# BW1098OAK_USB.net
KiCad netlist of a schematic drawn in Altium Designer
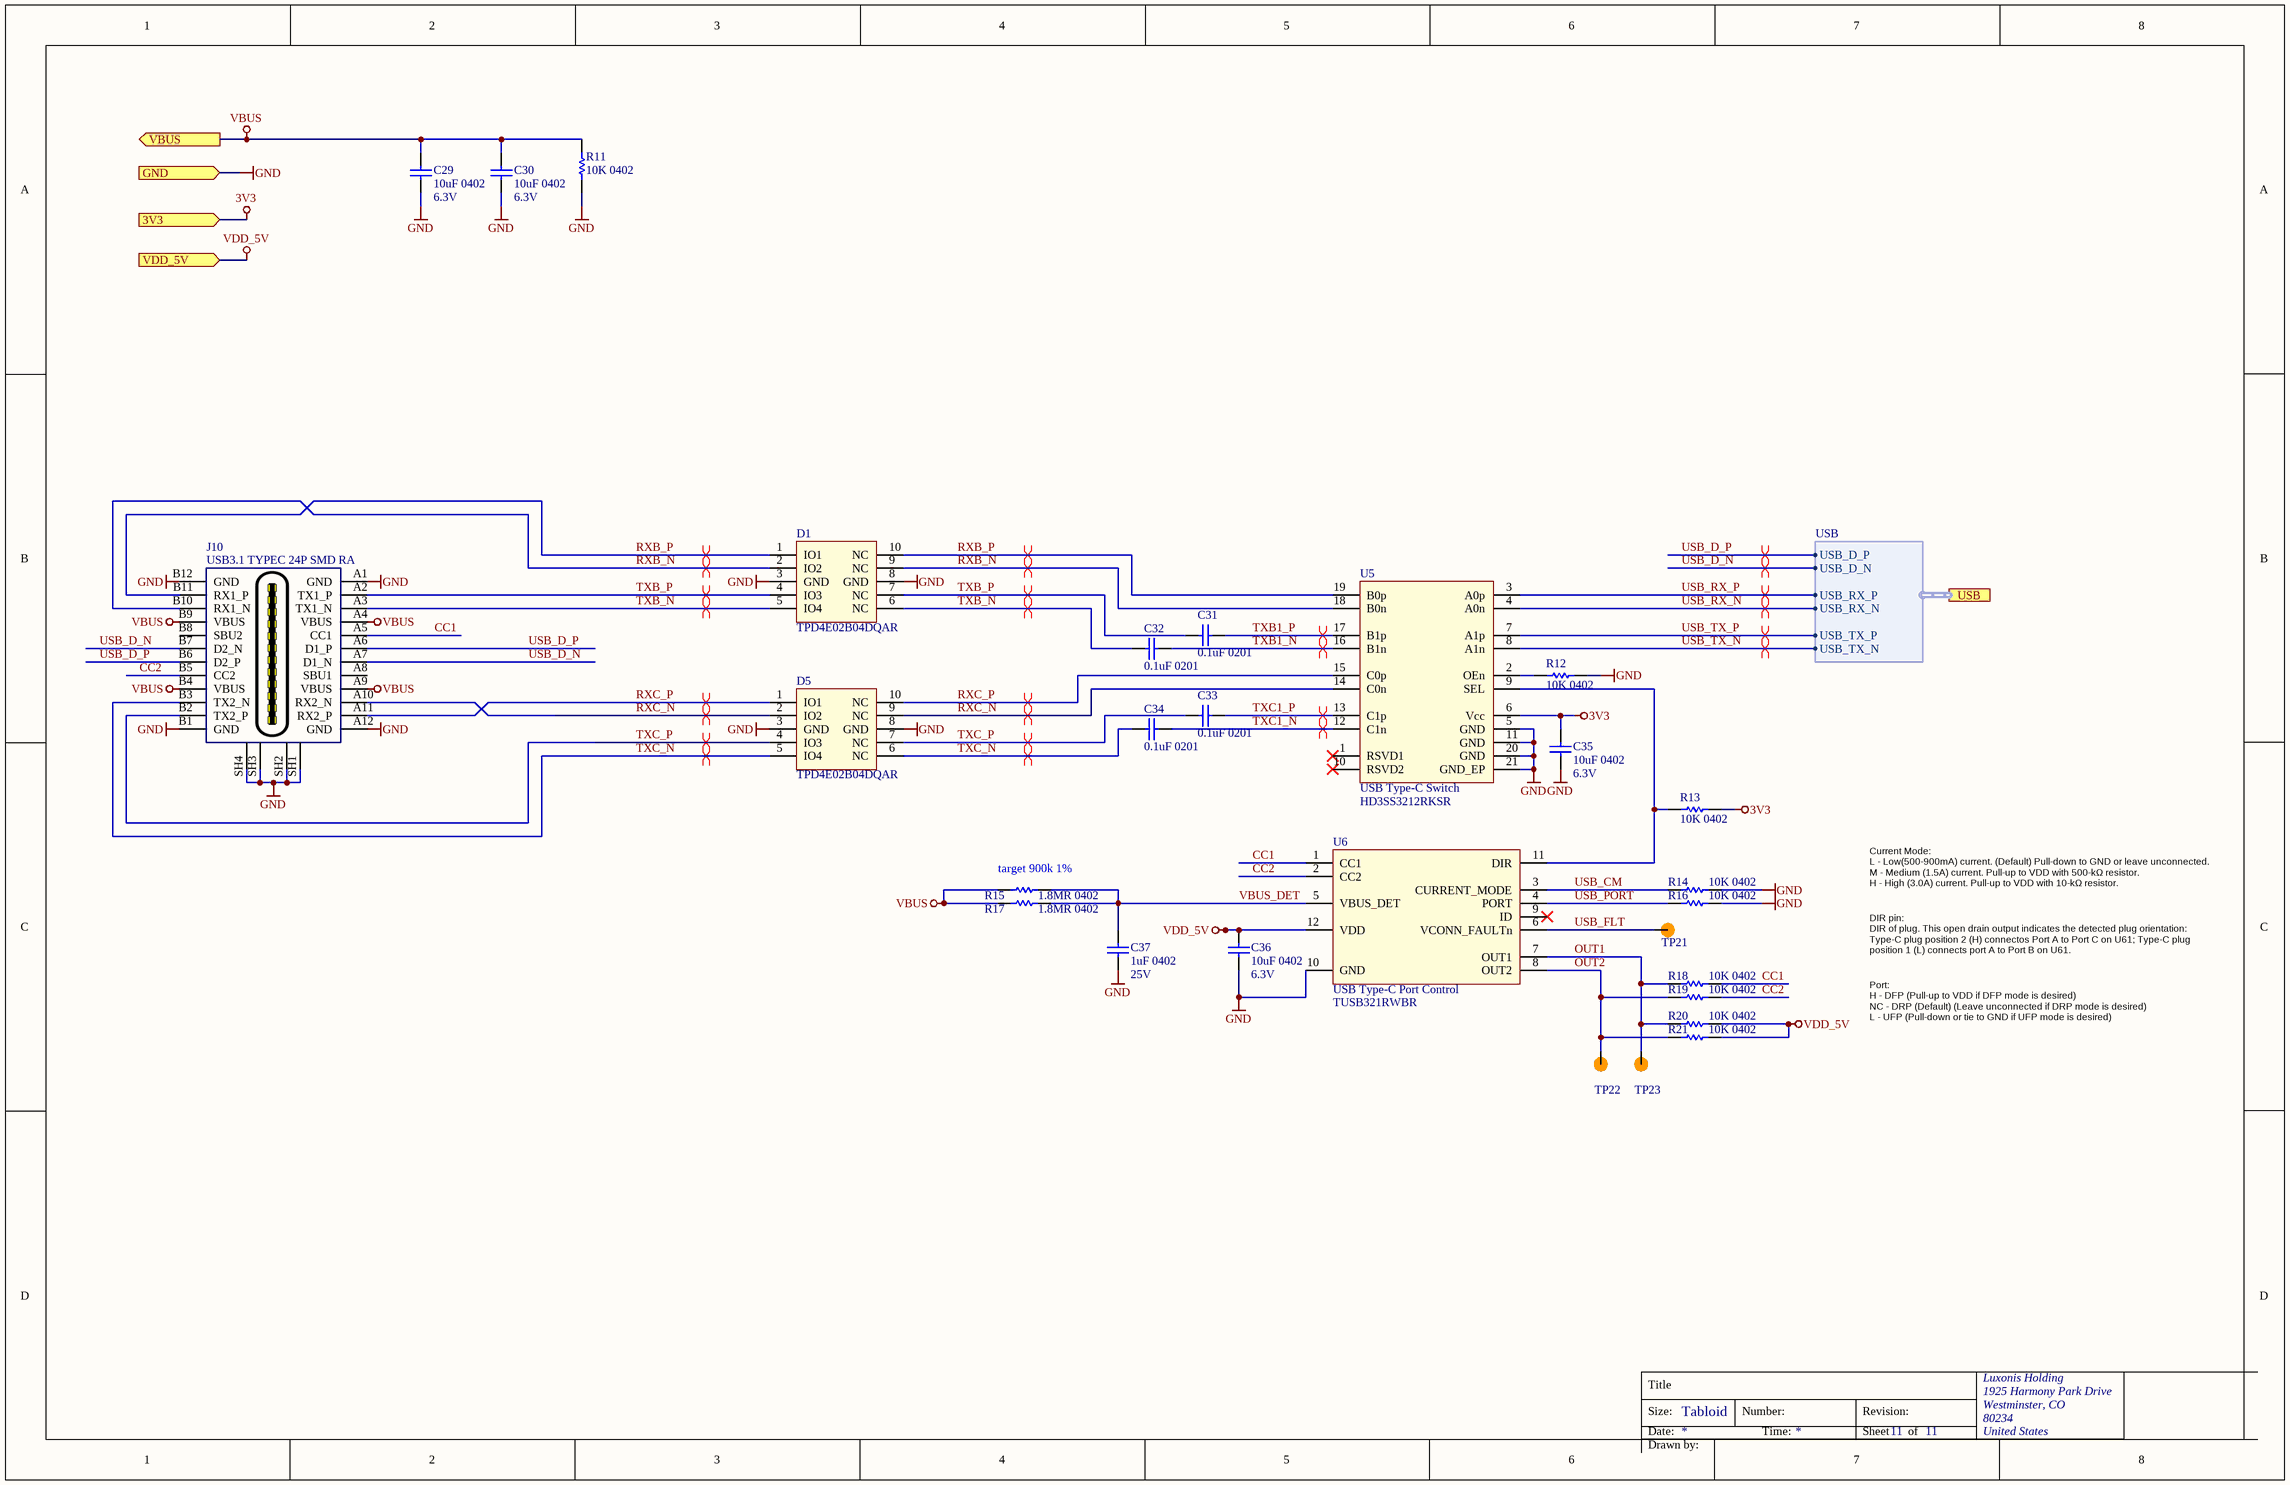
[diagram p0: BW1098OAK_USB.SchDoc]

(export (version "E")
  (design (tool "Eeschema 10.0.6"))
  (components
    (comp (ref "C29")
      (value "10uF 0402")
      (footprint "CAP_Altium_Vault_Generic:CAPC0402(1005)70_L")
      (description "CAP CER 10UF 6.3V X5R 0402 20%")
      (fields (field (name "TOLERANCE") "20%") (field (name "VOLTAGE RATING") "6.3V"))
      (libsource (lib "LuxonisMaster") (part "GRM155R60J106ME15D"))
    )
    (comp (ref "C30")
      (value "10uF 0402")
      (footprint "CAP_Altium_Vault_Generic:CAPC0402(1005)70_L")
      (description "CAP CER 10UF 6.3V X5R 0402 20%")
      (fields (field (name "TOLERANCE") "20%") (field (name "VOLTAGE RATING") "6.3V"))
      (libsource (lib "LuxonisMaster") (part "GRM155R60J106ME15D"))
    )
    (comp (ref "C31")
      (value "0.1uF 0201")
      (footprint "CAP_Altium_Vault_Generic:CAPC0201(0603)33_L")
      (description "CAP CER 0.1UF 10V X5R 0201")
      (fields (field (name "TOLERANCE") "10%") (field (name "VOLTAGE") "10V"))
      (libsource (lib "LuxonisMaster") (part "GRM033R61A104KE15D"))
    )
    (comp (ref "C32")
      (value "0.1uF 0201")
      (footprint "CAP_Altium_Vault_Generic:CAPC0201(0603)33_L")
      (description "CAP CER 0.1UF 10V X5R 0201")
      (fields (field (name "TOLERANCE") "10%") (field (name "VOLTAGE") "10V"))
      (libsource (lib "LuxonisMaster") (part "GRM033R61A104KE15D"))
    )
    (comp (ref "C33")
      (value "0.1uF 0201")
      (footprint "CAP_Altium_Vault_Generic:CAPC0201(0603)33_L")
      (description "CAP CER 0.1UF 10V X5R 0201")
      (fields (field (name "TOLERANCE") "10%") (field (name "VOLTAGE") "10V"))
      (libsource (lib "LuxonisMaster") (part "GRM033R61A104KE15D"))
    )
    (comp (ref "C34")
      (value "0.1uF 0201")
      (footprint "CAP_Altium_Vault_Generic:CAPC0201(0603)33_L")
      (description "CAP CER 0.1UF 10V X5R 0201")
      (fields (field (name "TOLERANCE") "10%") (field (name "VOLTAGE") "10V"))
      (libsource (lib "LuxonisMaster") (part "GRM033R61A104KE15D"))
    )
    (comp (ref "C35")
      (value "10uF 0402")
      (footprint "CAP_Altium_Vault_Generic:CAPC0402(1005)70_L")
      (description "CAP CER 10UF 6.3V X5R 0402 20%")
      (fields (field (name "TOLERANCE") "20%") (field (name "VOLTAGE RATING") "6.3V"))
      (libsource (lib "LuxonisMaster") (part "GRM155R60J106ME15D"))
    )
    (comp (ref "C36")
      (value "10uF 0402")
      (footprint "CAP_Altium_Vault_Generic:CAPC0402(1005)70_L")
      (description "CAP CER 10UF 6.3V X5R 0402 20%")
      (fields (field (name "TOLERANCE") "20%") (field (name "VOLTAGE RATING") "6.3V"))
      (libsource (lib "LuxonisMaster") (part "GRM155R60J106ME15D"))
    )
    (comp (ref "C37")
      (value "1uF 0402")
      (footprint "CAP_Altium_Vault_Generic:CAPC0402(1005)70_N")
      (description "CAP CER 1UF 25V X5R 0402 10%")
      (fields
        (field (name "TOLERANCE") "10%")
        (field (name "VOLTAGE") "25V")
        (field (name "VOLTAGE RATING") "25V")
      )
      (libsource (lib "LuxonisMaster") (part "GRM155R61E105KA12D"))
    )
    (comp (ref "D1")
      (value "TPD4E02B04DQAR")
      (footprint "LuxonisMaster:TPD4E02B04DQAR")
      (libsource (lib "LuxonisMaster") (part "TPD4E02B04DQAR"))
    )
    (comp (ref "D5")
      (value "TPD4E02B04DQAR")
      (footprint "LuxonisMaster:TPD4E02B04DQAR")
      (libsource (lib "LuxonisMaster") (part "TPD4E02B04DQAR"))
    )
    (comp (ref "J10")
      (value "USB3.1 TYPEC 24P SMD RA")
      (footprint "LuxonisMaster:105450-0101")
      (description "CONN RCP USB3.1 TYPEC 24P SMD RA")
      (libsource (lib "LuxonisMaster") (part "105450-0101"))
    )
    (comp (ref "R11")
      (value "10K 0402")
      (footprint "RES_Altium_Vault_Generic:RESC0402(1005)_L")
      (fields (field (name "TOLERANCE") "1%"))
      (libsource (lib "LuxonisMaster") (part "RC0402FR-1310KL"))
    )
    (comp (ref "R12")
      (value "10K 0402")
      (footprint "RES_Altium_Vault_Generic:RESC0402(1005)_L")
      (fields (field (name "TOLERANCE") "1%"))
      (libsource (lib "LuxonisMaster") (part "RC0402FR-1310KL"))
    )
    (comp (ref "R13")
      (value "10K 0402")
      (footprint "RES_Altium_Vault_Generic:RESC0402(1005)_L")
      (fields (field (name "TOLERANCE") "1%"))
      (libsource (lib "LuxonisMaster") (part "RC0402FR-1310KL"))
    )
    (comp (ref "R14")
      (value "10K 0402")
      (footprint "RES_Altium_Vault_Generic:RESC0402(1005)_L")
      (fields (field (name "TOLERANCE") "1%"))
      (libsource (lib "LuxonisMaster") (part "RC0402FR-1310KL"))
    )
    (comp (ref "R15")
      (value "1.8MR 0402")
      (footprint "RES_Altium_Vault_Generic:RESC0402(1005)_L")
      (description "RES SMD 1.8M OHM 1% 1/16W 0402")
      (fields (field (name "TOLERANCE") "1%"))
      (libsource (lib "LuxonisMaster") (part "CRCW04021M80FKED"))
    )
    (comp (ref "R16")
      (value "10K 0402")
      (footprint "RES_Altium_Vault_Generic:RESC0402(1005)_L")
      (fields (field (name "TOLERANCE") "1%"))
      (libsource (lib "LuxonisMaster") (part "RC0402FR-1310KL"))
    )
    (comp (ref "R17")
      (value "1.8MR 0402")
      (footprint "RES_Altium_Vault_Generic:RESC0402(1005)_L")
      (description "RES SMD 1.8M OHM 1% 1/16W 0402")
      (fields (field (name "TOLERANCE") "1%"))
      (libsource (lib "LuxonisMaster") (part "CRCW04021M80FKED"))
    )
    (comp (ref "R18")
      (value "10K 0402")
      (footprint "RES_Altium_Vault_Generic:RESC0402(1005)_L")
      (fields (field (name "TOLERANCE") "1%"))
      (libsource (lib "LuxonisMaster") (part "RC0402FR-1310KL"))
    )
    (comp (ref "R19")
      (value "10K 0402")
      (footprint "RES_Altium_Vault_Generic:RESC0402(1005)_L")
      (fields (field (name "TOLERANCE") "1%"))
      (libsource (lib "LuxonisMaster") (part "RC0402FR-1310KL"))
    )
    (comp (ref "R20")
      (value "10K 0402")
      (footprint "RES_Altium_Vault_Generic:RESC0402(1005)_L")
      (fields (field (name "TOLERANCE") "1%"))
      (libsource (lib "LuxonisMaster") (part "RC0402FR-1310KL"))
    )
    (comp (ref "R21")
      (value "10K 0402")
      (footprint "RES_Altium_Vault_Generic:RESC0402(1005)_L")
      (fields (field (name "TOLERANCE") "1%"))
      (libsource (lib "LuxonisMaster") (part "RC0402FR-1310KL"))
    )
    (comp (ref "TP21")
      (value "TP100_200_NS")
      (footprint "LuxonisMaster:TP100_200_NS")
      (libsource (lib "LuxonisMaster") (part "TEST_POINT"))
    )
    (comp (ref "TP22")
      (value "TP100_200_NS")
      (footprint "LuxonisMaster:TP100_200_NS")
      (libsource (lib "LuxonisMaster") (part "TEST_POINT"))
    )
    (comp (ref "TP23")
      (value "TP100_200_NS")
      (footprint "LuxonisMaster:TP100_200_NS")
      (libsource (lib "LuxonisMaster") (part "TEST_POINT"))
    )
    (comp (ref "U5")
      (value "USB Type-C Switch")
      (footprint "LuxonisMaster:HD3SS3212RKSR")
      (description "IC MUX 2:1 8 OHM 20VQFN")
      (fields (field (name "MANUFACTURER PART NUMBER 1") "HD3SS3212RKSR"))
      (libsource (lib "LuxonisMaster") (part "HD3SS3212RKSR"))
    )
    (comp (ref "U6")
      (value "USB Type-C Port Control")
      (footprint "LuxonisMaster:TUSB321RWBR")
      (description "IC USB PORT CONTROL TYPE-C 12X2Q")
      (fields (field (name "MANUFACTURER PART NUMBER 1") "TUSB321RWBR"))
      (libsource (lib "LuxonisMaster") (part "TUSB321RWBR"))
    )
  )
  (nets
    (net (code "2") (name "/CC1") (class "Default")
      (node (ref "J10") (pin "A5") (pinfunction "CC1_A5") (pintype "passive"))
      (node (ref "R18") (pin "2") (pinfunction "2_2") (pintype "passive"))
      (node (ref "U6") (pin "1") (pinfunction "CC1_1") (pintype "passive"))
    )
    (net (code "3") (name "/CC2") (class "Default")
      (node (ref "J10") (pin "B5") (pinfunction "CC2_B5") (pintype "passive"))
      (node (ref "R19") (pin "2") (pinfunction "2_2") (pintype "passive"))
      (node (ref "U6") (pin "2") (pinfunction "CC2_2") (pintype "passive"))
    )
    (net (code "4") (name "/OUT1") (class "Default")
      (node (ref "R18") (pin "1") (pinfunction "1_1") (pintype "passive"))
      (node (ref "R20") (pin "1") (pinfunction "1_1") (pintype "passive"))
      (node (ref "TP23") (pin "1") (pintype "passive"))
      (node (ref "U6") (pin "7") (pinfunction "OUT1_7") (pintype "passive"))
    )
    (net (code "5") (name "/OUT2") (class "Default")
      (node (ref "R19") (pin "1") (pinfunction "1_1") (pintype "passive"))
      (node (ref "R21") (pin "1") (pinfunction "1_1") (pintype "passive"))
      (node (ref "TP22") (pin "1") (pintype "passive"))
      (node (ref "U6") (pin "8") (pinfunction "OUT2_8") (pintype "passive"))
    )
    (net (code "6") (name "/RXB_N") (class "Default")
      (node (ref "D1") (pin "2") (pinfunction "IO2_2") (pintype "passive"))
      (node (ref "D1") (pin "9") (pinfunction "NC_9") (pintype "passive"))
      (node (ref "J10") (pin "B10") (pinfunction "RX1_N_B10") (pintype "passive"))
      (node (ref "U5") (pin "18") (pinfunction "B0n_18") (pintype "passive"))
    )
    (net (code "7") (name "/RXB_P") (class "Default")
      (node (ref "D1") (pin "1") (pinfunction "IO1_1") (pintype "passive"))
      (node (ref "D1") (pin "10") (pinfunction "NC_10") (pintype "passive"))
      (node (ref "J10") (pin "B11") (pinfunction "RX1_P_B11") (pintype "passive"))
      (node (ref "U5") (pin "19") (pinfunction "B0p_19") (pintype "passive"))
    )
    (net (code "8") (name "/RXC_N") (class "Default")
      (node (ref "D5") (pin "2") (pinfunction "IO2_2") (pintype "passive"))
      (node (ref "D5") (pin "9") (pinfunction "NC_9") (pintype "passive"))
      (node (ref "J10") (pin "A10") (pinfunction "RX2_N_A10") (pintype "passive"))
      (node (ref "U5") (pin "14") (pinfunction "C0n_14") (pintype "passive"))
    )
    (net (code "9") (name "/RXC_P") (class "Default")
      (node (ref "D5") (pin "1") (pinfunction "IO1_1") (pintype "passive"))
      (node (ref "D5") (pin "10") (pinfunction "NC_10") (pintype "passive"))
      (node (ref "J10") (pin "A11") (pinfunction "RX2_P_A11") (pintype "passive"))
      (node (ref "U5") (pin "15") (pinfunction "C0p_15") (pintype "passive"))
    )
    (net (code "10") (name "/TXB1_N") (class "Default")
      (node (ref "C32") (pin "2") (pinfunction "2_2") (pintype "passive"))
      (node (ref "U5") (pin "16") (pinfunction "B1n_16") (pintype "passive"))
    )
    (net (code "11") (name "/TXB1_P") (class "Default")
      (node (ref "C31") (pin "2") (pinfunction "2_2") (pintype "passive"))
      (node (ref "U5") (pin "17") (pinfunction "B1p_17") (pintype "passive"))
    )
    (net (code "12") (name "/TXB_N") (class "Default")
      (node (ref "C32") (pin "1") (pinfunction "1_1") (pintype "passive"))
      (node (ref "D1") (pin "5") (pinfunction "IO4_5") (pintype "passive"))
      (node (ref "D1") (pin "6") (pinfunction "NC_6") (pintype "passive"))
      (node (ref "J10") (pin "A3") (pinfunction "TX1_N_A3") (pintype "passive"))
    )
    (net (code "13") (name "/TXB_P") (class "Default")
      (node (ref "C31") (pin "1") (pinfunction "1_1") (pintype "passive"))
      (node (ref "D1") (pin "4") (pinfunction "IO3_4") (pintype "passive"))
      (node (ref "D1") (pin "7") (pinfunction "NC_7") (pintype "passive"))
      (node (ref "J10") (pin "A2") (pinfunction "TX1_P_A2") (pintype "passive"))
    )
    (net (code "14") (name "/TXC1_N") (class "Default")
      (node (ref "C34") (pin "2") (pinfunction "2_2") (pintype "passive"))
      (node (ref "U5") (pin "12") (pinfunction "C1n_12") (pintype "passive"))
    )
    (net (code "15") (name "/TXC1_P") (class "Default")
      (node (ref "C33") (pin "2") (pinfunction "2_2") (pintype "passive"))
      (node (ref "U5") (pin "13") (pinfunction "C1p_13") (pintype "passive"))
    )
    (net (code "16") (name "/TXC_N") (class "Default")
      (node (ref "C34") (pin "1") (pinfunction "1_1") (pintype "passive"))
      (node (ref "D5") (pin "5") (pinfunction "IO4_5") (pintype "passive"))
      (node (ref "D5") (pin "6") (pinfunction "NC_6") (pintype "passive"))
      (node (ref "J10") (pin "B3") (pinfunction "TX2_N_B3") (pintype "passive"))
    )
    (net (code "17") (name "/TXC_P") (class "Default")
      (node (ref "C33") (pin "1") (pinfunction "1_1") (pintype "passive"))
      (node (ref "D5") (pin "4") (pinfunction "IO3_4") (pintype "passive"))
      (node (ref "D5") (pin "7") (pinfunction "NC_7") (pintype "passive"))
      (node (ref "J10") (pin "B2") (pinfunction "TX2_P_B2") (pintype "passive"))
    )
    (net (code "18") (name "/USB_CM") (class "Default")
      (node (ref "R14") (pin "1") (pinfunction "1_1") (pintype "passive"))
      (node (ref "U6") (pin "3") (pinfunction "CURRENT_MODE_3") (pintype "passive"))
    )
    (net (code "19") (name "/USB_D_N") (class "Default")
      (node (ref "J10") (pin "A7") (pinfunction "D1_N_A7") (pintype "passive"))
      (node (ref "J10") (pin "B7") (pinfunction "D2_N_B7") (pintype "passive"))
    )
    (net (code "20") (name "/USB_D_P") (class "Default")
      (node (ref "J10") (pin "A6") (pinfunction "D1_P_A6") (pintype "passive"))
      (node (ref "J10") (pin "B6") (pinfunction "D2_P_B6") (pintype "passive"))
    )
    (net (code "21") (name "/USB_FLT") (class "Default")
      (node (ref "TP21") (pin "1") (pintype "passive"))
      (node (ref "U6") (pin "6") (pinfunction "VCONN_FAULTn_6") (pintype "passive"))
    )
    (net (code "22") (name "/USB_PORT") (class "Default")
      (node (ref "R16") (pin "1") (pinfunction "1_1") (pintype "passive"))
      (node (ref "U6") (pin "4") (pinfunction "PORT_4") (pintype "passive"))
    )
    (net (code "23") (name "/USB_RX_N") (class "Default")
      (node (ref "U5") (pin "4") (pinfunction "A0n_4") (pintype "passive"))
    )
    (net (code "24") (name "/USB_RX_P") (class "Default")
      (node (ref "U5") (pin "3") (pinfunction "A0p_3") (pintype "passive"))
    )
    (net (code "25") (name "/USB_TX_N") (class "Default")
      (node (ref "U5") (pin "8") (pinfunction "A1n_8") (pintype "passive"))
    )
    (net (code "26") (name "/USB_TX_P") (class "Default")
      (node (ref "U5") (pin "7") (pinfunction "A1p_7") (pintype "passive"))
    )
    (net (code "27") (name "/VBUS_DET") (class "Default")
      (node (ref "C37") (pin "2") (pinfunction "2_2") (pintype "passive"))
      (node (ref "R15") (pin "2") (pinfunction "2_2") (pintype "passive"))
      (node (ref "R17") (pin "2") (pinfunction "2_2") (pintype "passive"))
      (node (ref "U6") (pin "5") (pinfunction "VBUS_DET_5") (pintype "passive"))
    )
    (net (code "29") (name "3V3") (class "Default")
      (node (ref "C35") (pin "2") (pinfunction "2_2") (pintype "passive"))
      (node (ref "R13") (pin "2") (pinfunction "2_2") (pintype "passive"))
      (node (ref "U5") (pin "6") (pinfunction "Vcc_6") (pintype "passive"))
    )
    (net (code "30") (name "GND") (class "Default")
      (node (ref "C29") (pin "1") (pinfunction "1_1") (pintype "passive"))
      (node (ref "C30") (pin "1") (pinfunction "1_1") (pintype "passive"))
      (node (ref "C35") (pin "1") (pinfunction "1_1") (pintype "passive"))
      (node (ref "C36") (pin "1") (pinfunction "1_1") (pintype "passive"))
      (node (ref "C37") (pin "1") (pinfunction "1_1") (pintype "passive"))
      (node (ref "D1") (pin "3") (pinfunction "GND_3") (pintype "passive"))
      (node (ref "D1") (pin "8") (pinfunction "GND_8") (pintype "passive"))
      (node (ref "D5") (pin "3") (pinfunction "GND_3") (pintype "passive"))
      (node (ref "D5") (pin "8") (pinfunction "GND_8") (pintype "passive"))
      (node (ref "J10") (pin "A1") (pinfunction "GND_A1") (pintype "passive"))
      (node (ref "J10") (pin "A12") (pinfunction "GND_A12") (pintype "passive"))
      (node (ref "J10") (pin "B1") (pinfunction "GND_B1") (pintype "passive"))
      (node (ref "J10") (pin "B12") (pinfunction "GND_B12") (pintype "passive"))
      (node (ref "J10") (pin "SH1") (pinfunction "SH_SH1") (pintype "passive"))
      (node (ref "J10") (pin "SH2") (pinfunction "SH_SH2") (pintype "passive"))
      (node (ref "J10") (pin "SH3") (pinfunction "SH_SH3") (pintype "passive"))
      (node (ref "J10") (pin "SH4") (pinfunction "SH_SH4") (pintype "passive"))
      (node (ref "R11") (pin "1") (pinfunction "1_1") (pintype "passive"))
      (node (ref "R12") (pin "2") (pinfunction "2_2") (pintype "passive"))
      (node (ref "R14") (pin "2") (pinfunction "2_2") (pintype "passive"))
      (node (ref "R16") (pin "2") (pinfunction "2_2") (pintype "passive"))
      (node (ref "U5") (pin "11") (pinfunction "GND_11") (pintype "passive"))
      (node (ref "U5") (pin "20") (pinfunction "GND_20") (pintype "passive"))
      (node (ref "U5") (pin "21") (pinfunction "GND_EP_21") (pintype "passive"))
      (node (ref "U5") (pin "5") (pinfunction "GND_5") (pintype "passive"))
      (node (ref "U6") (pin "10") (pinfunction "GND_10") (pintype "passive"))
    )
    (net (code "31") (name "Net-(U5-OEn)") (class "Default")
      (node (ref "R12") (pin "1") (pinfunction "1_1") (pintype "passive"))
      (node (ref "U5") (pin "2") (pinfunction "OEn_2") (pintype "passive"))
    )
    (net (code "32") (name "Net-(U5-SEL)") (class "Default")
      (node (ref "R13") (pin "1") (pinfunction "1_1") (pintype "passive"))
      (node (ref "U5") (pin "9") (pinfunction "SEL_9") (pintype "passive"))
      (node (ref "U6") (pin "11") (pinfunction "DIR_11") (pintype "passive"))
    )
    (net (code "33") (name "VBUS") (class "Default")
      (node (ref "C29") (pin "2") (pinfunction "2_2") (pintype "passive"))
      (node (ref "C30") (pin "2") (pinfunction "2_2") (pintype "passive"))
      (node (ref "J10") (pin "A4") (pinfunction "VBUS_A4") (pintype "passive"))
      (node (ref "J10") (pin "A9") (pinfunction "VBUS_A9") (pintype "passive"))
      (node (ref "J10") (pin "B4") (pinfunction "VBUS_B4") (pintype "passive"))
      (node (ref "J10") (pin "B9") (pinfunction "VBUS_B9") (pintype "passive"))
      (node (ref "R11") (pin "2") (pinfunction "2_2") (pintype "passive"))
      (node (ref "R15") (pin "1") (pinfunction "1_1") (pintype "passive"))
      (node (ref "R17") (pin "1") (pinfunction "1_1") (pintype "passive"))
    )
    (net (code "34") (name "VDD_5V") (class "Default")
      (node (ref "C36") (pin "2") (pinfunction "2_2") (pintype "passive"))
      (node (ref "R20") (pin "2") (pinfunction "2_2") (pintype "passive"))
      (node (ref "R21") (pin "2") (pinfunction "2_2") (pintype "passive"))
      (node (ref "U6") (pin "12") (pinfunction "VDD_12") (pintype "passive"))
    )
    (net (code "35") (name "unconnected-(J10-SBU1-PadA8)") (class "Default")
      (node (ref "J10") (pin "A8") (pinfunction "SBU1_A8") (pintype "passive"))
    )
    (net (code "36") (name "unconnected-(J10-SBU2-PadB8)") (class "Default")
      (node (ref "J10") (pin "B8") (pinfunction "SBU2_B8") (pintype "passive"))
    )
    (net (code "37") (name "unconnected-(U5-RSVD1-Pad1)") (class "Default")
      (node (ref "U5") (pin "1") (pinfunction "RSVD1_1") (pintype "passive+no_connect"))
    )
    (net (code "38") (name "unconnected-(U5-RSVD2-Pad10)") (class "Default")
      (node (ref "U5") (pin "10") (pinfunction "RSVD2_10") (pintype "passive+no_connect"))
    )
    (net (code "39") (name "unconnected-(U6-ID-Pad9)") (class "Default")
      (node (ref "U6") (pin "9") (pinfunction "ID_9") (pintype "passive+no_connect"))
    )
  )
)
